# board.net
KiCad netlist of a schematic drawn in EAGLE
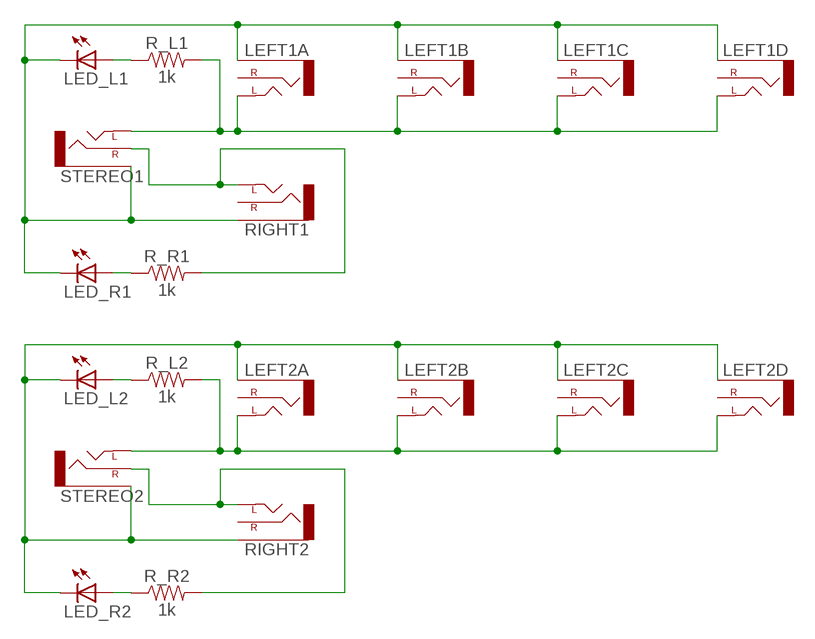
[diagram p0: schematic, sheet 1]

(export (version "E")
  (design (tool "Eeschema 10.0.6"))
  (components
    (comp (ref "LED_L1")
      (value "LED3MM")
      (footprint "eagle-import:LED3MM")
      (libsource (lib "eagle-import") (part "LED3MM"))
    )
    (comp (ref "LED_L2")
      (value "LED3MM")
      (footprint "eagle-import:LED3MM")
      (libsource (lib "eagle-import") (part "LED3MM"))
    )
    (comp (ref "LED_R1")
      (value "LED3MM")
      (footprint "eagle-import:LED3MM")
      (libsource (lib "eagle-import") (part "LED3MM"))
    )
    (comp (ref "LED_R2")
      (value "LED3MM")
      (footprint "eagle-import:LED3MM")
      (libsource (lib "eagle-import") (part "LED3MM"))
    )
    (comp (ref "LEFT1A")
      (value "THONKI-STEREO")
      (footprint "eagle-import:WQP-PJ366ST_JACK")
      (libsource (lib "eagle-import") (part "THONKI-STEREO"))
    )
    (comp (ref "LEFT1B")
      (value "THONKI-STEREO")
      (footprint "eagle-import:WQP-PJ366ST_JACK")
      (libsource (lib "eagle-import") (part "THONKI-STEREO"))
    )
    (comp (ref "LEFT1C")
      (value "THONKI-STEREO")
      (footprint "eagle-import:WQP-PJ366ST_JACK")
      (libsource (lib "eagle-import") (part "THONKI-STEREO"))
    )
    (comp (ref "LEFT1D")
      (value "THONKI-STEREO")
      (footprint "eagle-import:WQP-PJ366ST_JACK")
      (libsource (lib "eagle-import") (part "THONKI-STEREO"))
    )
    (comp (ref "LEFT2A")
      (value "THONKI-STEREO")
      (footprint "eagle-import:WQP-PJ366ST_JACK")
      (libsource (lib "eagle-import") (part "THONKI-STEREO"))
    )
    (comp (ref "LEFT2B")
      (value "THONKI-STEREO")
      (footprint "eagle-import:WQP-PJ366ST_JACK")
      (libsource (lib "eagle-import") (part "THONKI-STEREO"))
    )
    (comp (ref "LEFT2C")
      (value "THONKI-STEREO")
      (footprint "eagle-import:WQP-PJ366ST_JACK")
      (libsource (lib "eagle-import") (part "THONKI-STEREO"))
    )
    (comp (ref "LEFT2D")
      (value "THONKI-STEREO")
      (footprint "eagle-import:WQP-PJ366ST_JACK")
      (libsource (lib "eagle-import") (part "THONKI-STEREO"))
    )
    (comp (ref "RIGHT1")
      (value "THONKI-STEREO")
      (footprint "eagle-import:WQP-PJ366ST_JACK")
      (libsource (lib "eagle-import") (part "THONKI-STEREO"))
    )
    (comp (ref "RIGHT2")
      (value "THONKI-STEREO")
      (footprint "eagle-import:WQP-PJ366ST_JACK")
      (libsource (lib "eagle-import") (part "THONKI-STEREO"))
    )
    (comp (ref "R_L1")
      (value "1k")
      (footprint "eagle-import:AXIAL-0.3")
      (libsource (lib "eagle-import") (part "1KOHM-HORIZ-1/4W-1%"))
    )
    (comp (ref "R_L2")
      (value "1k")
      (footprint "eagle-import:AXIAL-0.3")
      (libsource (lib "eagle-import") (part "1KOHM-HORIZ-1/4W-1%"))
    )
    (comp (ref "R_R1")
      (value "1k")
      (footprint "eagle-import:AXIAL-0.3")
      (libsource (lib "eagle-import") (part "1KOHM-HORIZ-1/4W-1%"))
    )
    (comp (ref "R_R2")
      (value "1k")
      (footprint "eagle-import:AXIAL-0.3")
      (libsource (lib "eagle-import") (part "1KOHM-HORIZ-1/4W-1%"))
    )
    (comp (ref "STEREO1")
      (value "THONKI-STEREO")
      (footprint "eagle-import:WQP-PJ366ST_JACK")
      (libsource (lib "eagle-import") (part "THONKI-STEREO"))
    )
    (comp (ref "STEREO2")
      (value "THONKI-STEREO")
      (footprint "eagle-import:WQP-PJ366ST_JACK")
      (libsource (lib "eagle-import") (part "THONKI-STEREO"))
    )
  )
  (nets
    (net (code "1") (name "Net-(LED_L1-C)") (class "Default")
      (node (ref "LED_L1") (pin "K") (pinfunction "C_K") (pintype "passive"))
      (node (ref "LED_R1") (pin "K") (pinfunction "C_K") (pintype "passive"))
      (node (ref "LEFT1A") (pin "P$3_SLEEVE") (pinfunction "SLEEVE_P$3_SLEEVE") (pintype "bidirectional"))
      (node (ref "LEFT1B") (pin "P$3_SLEEVE") (pinfunction "SLEEVE_P$3_SLEEVE") (pintype "bidirectional"))
      (node (ref "LEFT1C") (pin "P$3_SLEEVE") (pinfunction "SLEEVE_P$3_SLEEVE") (pintype "bidirectional"))
      (node (ref "LEFT1D") (pin "P$3_SLEEVE") (pinfunction "SLEEVE_P$3_SLEEVE") (pintype "bidirectional"))
      (node (ref "RIGHT1") (pin "P$3_SLEEVE") (pinfunction "SLEEVE_P$3_SLEEVE") (pintype "bidirectional"))
      (node (ref "STEREO1") (pin "P$3_SLEEVE") (pinfunction "SLEEVE_P$3_SLEEVE") (pintype "bidirectional"))
    )
    (net (code "2") (name "Net-(LED_L2-C)") (class "Default")
      (node (ref "LED_L2") (pin "K") (pinfunction "C_K") (pintype "passive"))
      (node (ref "LED_R2") (pin "K") (pinfunction "C_K") (pintype "passive"))
      (node (ref "LEFT2A") (pin "P$3_SLEEVE") (pinfunction "SLEEVE_P$3_SLEEVE") (pintype "bidirectional"))
      (node (ref "LEFT2B") (pin "P$3_SLEEVE") (pinfunction "SLEEVE_P$3_SLEEVE") (pintype "bidirectional"))
      (node (ref "LEFT2C") (pin "P$3_SLEEVE") (pinfunction "SLEEVE_P$3_SLEEVE") (pintype "bidirectional"))
      (node (ref "LEFT2D") (pin "P$3_SLEEVE") (pinfunction "SLEEVE_P$3_SLEEVE") (pintype "bidirectional"))
      (node (ref "RIGHT2") (pin "P$3_SLEEVE") (pinfunction "SLEEVE_P$3_SLEEVE") (pintype "bidirectional"))
      (node (ref "STEREO2") (pin "P$3_SLEEVE") (pinfunction "SLEEVE_P$3_SLEEVE") (pintype "bidirectional"))
    )
    (net (code "3") (name "Net-(LEFT1A-LEFT)") (class "Default")
      (node (ref "LEFT1A") (pin "P$1_TIP") (pinfunction "LEFT_P$1_TIP") (pintype "bidirectional"))
      (node (ref "LEFT1B") (pin "P$1_TIP") (pinfunction "LEFT_P$1_TIP") (pintype "bidirectional"))
      (node (ref "LEFT1C") (pin "P$1_TIP") (pinfunction "LEFT_P$1_TIP") (pintype "bidirectional"))
      (node (ref "LEFT1D") (pin "P$1_TIP") (pinfunction "LEFT_P$1_TIP") (pintype "bidirectional"))
      (node (ref "R_L1") (pin "P$2") (pinfunction "2_P$2") (pintype "passive"))
      (node (ref "STEREO1") (pin "P$1_TIP") (pinfunction "LEFT_P$1_TIP") (pintype "bidirectional"))
    )
    (net (code "4") (name "Net-(LEFT2A-LEFT)") (class "Default")
      (node (ref "LEFT2A") (pin "P$1_TIP") (pinfunction "LEFT_P$1_TIP") (pintype "bidirectional"))
      (node (ref "LEFT2B") (pin "P$1_TIP") (pinfunction "LEFT_P$1_TIP") (pintype "bidirectional"))
      (node (ref "LEFT2C") (pin "P$1_TIP") (pinfunction "LEFT_P$1_TIP") (pintype "bidirectional"))
      (node (ref "LEFT2D") (pin "P$1_TIP") (pinfunction "LEFT_P$1_TIP") (pintype "bidirectional"))
      (node (ref "R_L2") (pin "P$2") (pinfunction "2_P$2") (pintype "passive"))
      (node (ref "STEREO2") (pin "P$1_TIP") (pinfunction "LEFT_P$1_TIP") (pintype "bidirectional"))
    )
    (net (code "5") (name "Net-(RIGHT1-LEFT)") (class "Default")
      (node (ref "RIGHT1") (pin "P$1_TIP") (pinfunction "LEFT_P$1_TIP") (pintype "bidirectional"))
      (node (ref "R_R1") (pin "P$2") (pinfunction "2_P$2") (pintype "passive"))
      (node (ref "STEREO1") (pin "P$2_SWITCH") (pinfunction "RIGHT_P$2_SWITCH") (pintype "bidirectional"))
    )
    (net (code "6") (name "Net-(RIGHT2-LEFT)") (class "Default")
      (node (ref "RIGHT2") (pin "P$1_TIP") (pinfunction "LEFT_P$1_TIP") (pintype "bidirectional"))
      (node (ref "R_R2") (pin "P$2") (pinfunction "2_P$2") (pintype "passive"))
      (node (ref "STEREO2") (pin "P$2_SWITCH") (pinfunction "RIGHT_P$2_SWITCH") (pintype "bidirectional"))
    )
    (net (code "7") (name "Net-(R_L1-1)") (class "Default")
      (node (ref "LED_L1") (pin "A") (pinfunction "A_A") (pintype "passive"))
      (node (ref "R_L1") (pin "P$1") (pinfunction "1_P$1") (pintype "passive"))
    )
    (net (code "8") (name "Net-(R_L2-1)") (class "Default")
      (node (ref "LED_L2") (pin "A") (pinfunction "A_A") (pintype "passive"))
      (node (ref "R_L2") (pin "P$1") (pinfunction "1_P$1") (pintype "passive"))
    )
    (net (code "9") (name "Net-(R_R1-1)") (class "Default")
      (node (ref "LED_R1") (pin "A") (pinfunction "A_A") (pintype "passive"))
      (node (ref "R_R1") (pin "P$1") (pinfunction "1_P$1") (pintype "passive"))
    )
    (net (code "10") (name "Net-(R_R2-1)") (class "Default")
      (node (ref "LED_R2") (pin "A") (pinfunction "A_A") (pintype "passive"))
      (node (ref "R_R2") (pin "P$1") (pinfunction "1_P$1") (pintype "passive"))
    )
    (net (code "11") (name "unconnected-(LEFT1A-RIGHT-PadP$2_SWITCH)") (class "Default")
      (node (ref "LEFT1A") (pin "P$2_SWITCH") (pinfunction "RIGHT_P$2_SWITCH") (pintype "bidirectional"))
    )
    (net (code "12") (name "unconnected-(LEFT1B-RIGHT-PadP$2_SWITCH)") (class "Default")
      (node (ref "LEFT1B") (pin "P$2_SWITCH") (pinfunction "RIGHT_P$2_SWITCH") (pintype "bidirectional"))
    )
    (net (code "13") (name "unconnected-(LEFT1C-RIGHT-PadP$2_SWITCH)") (class "Default")
      (node (ref "LEFT1C") (pin "P$2_SWITCH") (pinfunction "RIGHT_P$2_SWITCH") (pintype "bidirectional"))
    )
    (net (code "14") (name "unconnected-(LEFT1D-RIGHT-PadP$2_SWITCH)") (class "Default")
      (node (ref "LEFT1D") (pin "P$2_SWITCH") (pinfunction "RIGHT_P$2_SWITCH") (pintype "bidirectional"))
    )
    (net (code "15") (name "unconnected-(LEFT2A-RIGHT-PadP$2_SWITCH)") (class "Default")
      (node (ref "LEFT2A") (pin "P$2_SWITCH") (pinfunction "RIGHT_P$2_SWITCH") (pintype "bidirectional"))
    )
    (net (code "16") (name "unconnected-(LEFT2B-RIGHT-PadP$2_SWITCH)") (class "Default")
      (node (ref "LEFT2B") (pin "P$2_SWITCH") (pinfunction "RIGHT_P$2_SWITCH") (pintype "bidirectional"))
    )
    (net (code "17") (name "unconnected-(LEFT2C-RIGHT-PadP$2_SWITCH)") (class "Default")
      (node (ref "LEFT2C") (pin "P$2_SWITCH") (pinfunction "RIGHT_P$2_SWITCH") (pintype "bidirectional"))
    )
    (net (code "18") (name "unconnected-(LEFT2D-RIGHT-PadP$2_SWITCH)") (class "Default")
      (node (ref "LEFT2D") (pin "P$2_SWITCH") (pinfunction "RIGHT_P$2_SWITCH") (pintype "bidirectional"))
    )
    (net (code "19") (name "unconnected-(RIGHT1-RIGHT-PadP$2_SWITCH)") (class "Default")
      (node (ref "RIGHT1") (pin "P$2_SWITCH") (pinfunction "RIGHT_P$2_SWITCH") (pintype "bidirectional"))
    )
    (net (code "20") (name "unconnected-(RIGHT2-RIGHT-PadP$2_SWITCH)") (class "Default")
      (node (ref "RIGHT2") (pin "P$2_SWITCH") (pinfunction "RIGHT_P$2_SWITCH") (pintype "bidirectional"))
    )
  )
)
